# D1-Mini_Adapter.net
KiCad netlist of a schematic drawn in EAGLE
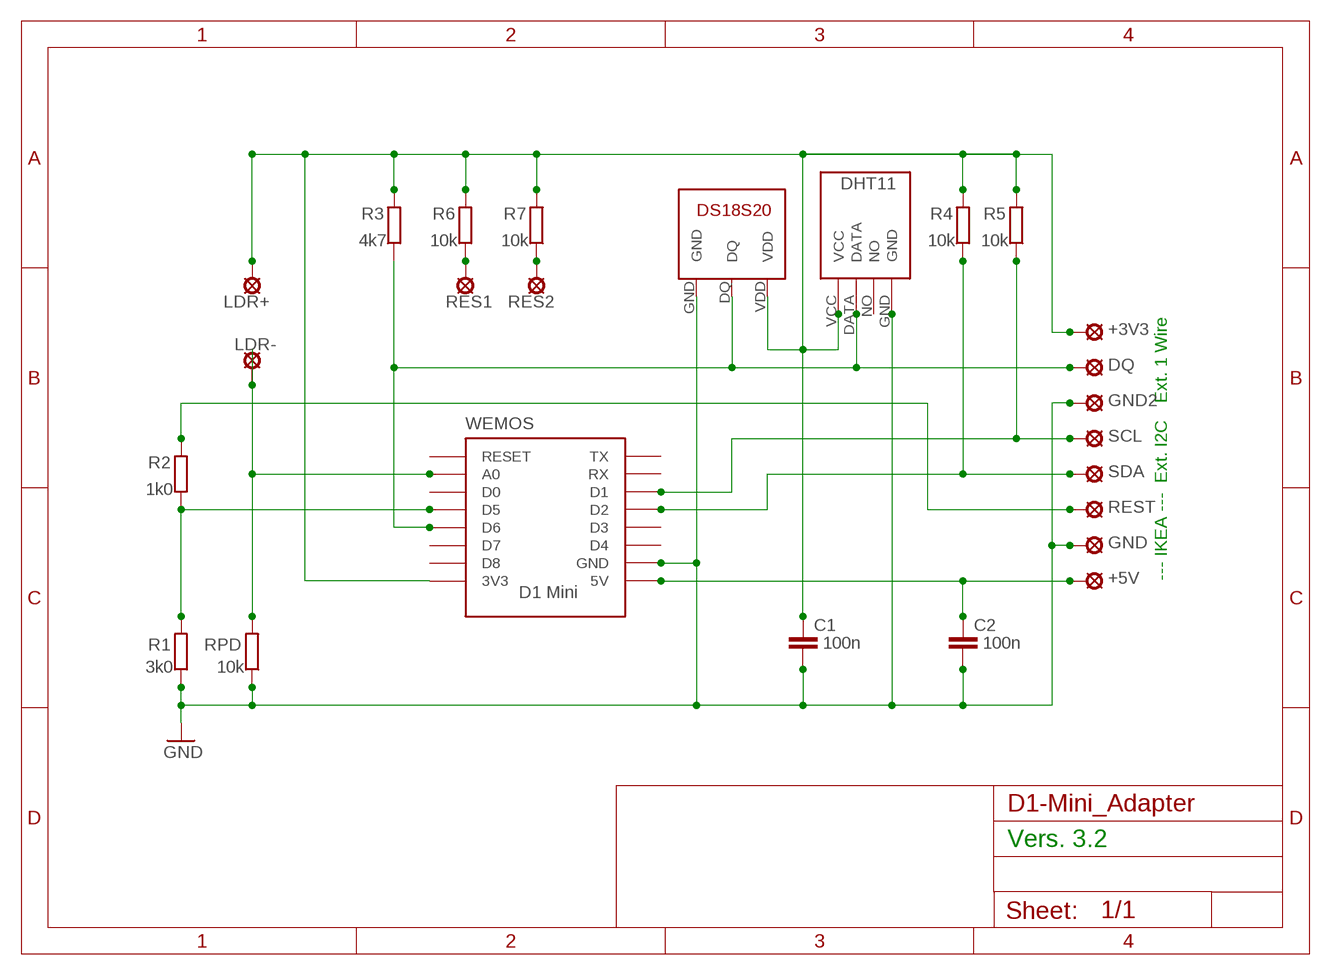
[diagram p0: schematic, sheet 1]

(export (version "E")
  (design (tool "Eeschema 10.0.6"))
  (components
    (comp (ref "+3V3")
      (value "SE13")
      (footprint "eagle-import:SE13")
      (libsource (lib "eagle-import") (part "SE13"))
    )
    (comp (ref "+5V")
      (value "SE13")
      (footprint "eagle-import:SE13")
      (libsource (lib "eagle-import") (part "SE13"))
    )
    (comp (ref "C1")
      (value "100n")
      (footprint "eagle-import:C025_050-045X075")
      (libsource (lib "eagle-import") (part "C-EU025_050-045X075"))
    )
    (comp (ref "C2")
      (value "100n")
      (footprint "eagle-import:C025_050-045X075")
      (libsource (lib "eagle-import") (part "C-EU025_050-045X075"))
    )
    (comp (ref "DQ")
      (value "SE13")
      (footprint "eagle-import:SE13")
      (libsource (lib "eagle-import") (part "SE13"))
    )
    (comp (ref "DS1820")
      (value "DS18S20")
      (footprint "eagle-import:DS18S20-PACKAGE")
      (libsource (lib "eagle-import") (part "DS18S20"))
    )
    (comp (ref "GND")
      (value "SE13")
      (footprint "eagle-import:SE13")
      (libsource (lib "eagle-import") (part "SE13"))
    )
    (comp (ref "GND2")
      (value "SE13")
      (footprint "eagle-import:SE13")
      (libsource (lib "eagle-import") (part "SE13"))
    )
    (comp (ref "LDR+")
      (value "SE13")
      (footprint "eagle-import:SE13")
      (libsource (lib "eagle-import") (part "SE13"))
    )
    (comp (ref "LDR-")
      (value "SE13")
      (footprint "eagle-import:SE13")
      (libsource (lib "eagle-import") (part "SE13"))
    )
    (comp (ref "R1")
      (value "3k0")
      (footprint "eagle-import:0207_10")
      (libsource (lib "eagle-import") (part "R-EU_0207/10"))
    )
    (comp (ref "R2")
      (value "1k0")
      (footprint "eagle-import:0207_10")
      (libsource (lib "eagle-import") (part "R-EU_0207/10"))
    )
    (comp (ref "R3")
      (value "4k7")
      (footprint "eagle-import:0207_10")
      (libsource (lib "eagle-import") (part "R-EU_0207/10"))
    )
    (comp (ref "R4")
      (value "10k")
      (footprint "eagle-import:0207_10")
      (libsource (lib "eagle-import") (part "R-EU_0207/10"))
    )
    (comp (ref "R5")
      (value "10k")
      (footprint "eagle-import:0207_10")
      (libsource (lib "eagle-import") (part "R-EU_0207/10"))
    )
    (comp (ref "R6")
      (value "10k")
      (footprint "eagle-import:0207_10")
      (libsource (lib "eagle-import") (part "R-EU_0207/10"))
    )
    (comp (ref "R7")
      (value "10k")
      (footprint "eagle-import:0207_10")
      (libsource (lib "eagle-import") (part "R-EU_0207/10"))
    )
    (comp (ref "RES1")
      (value "SE13")
      (footprint "eagle-import:SE13")
      (libsource (lib "eagle-import") (part "SE13"))
    )
    (comp (ref "RES2")
      (value "SE13")
      (footprint "eagle-import:SE13")
      (libsource (lib "eagle-import") (part "SE13"))
    )
    (comp (ref "REST")
      (value "SE13")
      (footprint "eagle-import:SE13")
      (libsource (lib "eagle-import") (part "SE13"))
    )
    (comp (ref "RPD")
      (value "10k")
      (footprint "eagle-import:0207_10")
      (libsource (lib "eagle-import") (part "R-EU_0207/10"))
    )
    (comp (ref "SCL")
      (value "SE13")
      (footprint "eagle-import:SE13")
      (libsource (lib "eagle-import") (part "SE13"))
    )
    (comp (ref "SDA")
      (value "SE13")
      (footprint "eagle-import:SE13")
      (libsource (lib "eagle-import") (part "SE13"))
    )
    (comp (ref "U$1")
      (value "DHT11-PION.")
      (footprint "eagle-import:DHT11-PION.")
      (libsource (lib "eagle-import") (part "DHT11-PION."))
    )
    (comp (ref "WEMOS")
      (value "D1 Mini")
      (footprint "eagle-import:WEMOS-D1-MINI")
      (libsource (lib "eagle-import") (part "WEMOS-D1-MINI"))
    )
  )
  (nets
    (net (code "1") (name "GND") (class "Default")
      (node (ref "C1") (pin "2") (pinfunction "2_2") (pintype "passive"))
      (node (ref "C2") (pin "2") (pinfunction "2_2") (pintype "passive"))
      (node (ref "DS1820") (pin "GND") (pinfunction "GND_GND") (pintype "power_in"))
      (node (ref "GND") (pin "MP") (pinfunction "MP_MP") (pintype "passive"))
      (node (ref "GND2") (pin "MP") (pinfunction "MP_MP") (pintype "passive"))
      (node (ref "R1") (pin "1") (pinfunction "1_1") (pintype "passive"))
      (node (ref "RPD") (pin "1") (pinfunction "1_1") (pintype "passive"))
      (node (ref "U$1") (pin "GND") (pinfunction "GND_GND") (pintype "bidirectional"))
      (node (ref "WEMOS") (pin "GND") (pinfunction "GND_GND") (pintype "bidirectional"))
    )
    (net (code "2") (name "Net-(+3V3-PadMP)") (class "Default")
      (node (ref "+3V3") (pin "MP") (pinfunction "MP_MP") (pintype "passive"))
      (node (ref "C1") (pin "1") (pinfunction "1_1") (pintype "passive"))
      (node (ref "DS1820") (pin "VDD") (pinfunction "VDD_VDD") (pintype "power_in"))
      (node (ref "LDR+") (pin "MP") (pinfunction "MP_MP") (pintype "passive"))
      (node (ref "R3") (pin "2") (pinfunction "2_2") (pintype "passive"))
      (node (ref "R4") (pin "2") (pinfunction "2_2") (pintype "passive"))
      (node (ref "R5") (pin "2") (pinfunction "2_2") (pintype "passive"))
      (node (ref "R6") (pin "2") (pinfunction "2_2") (pintype "passive"))
      (node (ref "R7") (pin "2") (pinfunction "2_2") (pintype "passive"))
      (node (ref "U$1") (pin "VCC") (pinfunction "VCC_VCC") (pintype "bidirectional"))
      (node (ref "WEMOS") (pin "3V3") (pinfunction "3V3_3V3") (pintype "bidirectional"))
    )
    (net (code "3") (name "Net-(+5V-PadMP)") (class "Default")
      (node (ref "+5V") (pin "MP") (pinfunction "MP_MP") (pintype "passive"))
      (node (ref "C2") (pin "1") (pinfunction "1_1") (pintype "passive"))
      (node (ref "WEMOS") (pin "5V") (pinfunction "5V_5V") (pintype "bidirectional"))
    )
    (net (code "4") (name "Net-(DQ-PadMP)") (class "Default")
      (node (ref "DQ") (pin "MP") (pinfunction "MP_MP") (pintype "passive"))
      (node (ref "DS1820") (pin "DQ") (pinfunction "DQ_DQ") (pintype "bidirectional"))
      (node (ref "R3") (pin "1") (pinfunction "1_1") (pintype "passive"))
      (node (ref "U$1") (pin "DATA") (pinfunction "DATA_DATA") (pintype "bidirectional"))
      (node (ref "WEMOS") (pin "D6") (pinfunction "D6_D6") (pintype "bidirectional"))
    )
    (net (code "5") (name "Net-(LDR--PadMP)") (class "Default")
      (node (ref "LDR-") (pin "MP") (pinfunction "MP_MP") (pintype "passive"))
      (node (ref "RPD") (pin "2") (pinfunction "2_2") (pintype "passive"))
      (node (ref "WEMOS") (pin "A0") (pinfunction "A0_A0") (pintype "bidirectional"))
    )
    (net (code "6") (name "Net-(R1-Pad2)") (class "Default")
      (node (ref "R1") (pin "2") (pinfunction "2_2") (pintype "passive"))
      (node (ref "R2") (pin "1") (pinfunction "1_1") (pintype "passive"))
      (node (ref "WEMOS") (pin "D5") (pinfunction "D5_D5") (pintype "bidirectional"))
    )
    (net (code "7") (name "Net-(R2-Pad2)") (class "Default")
      (node (ref "R2") (pin "2") (pinfunction "2_2") (pintype "passive"))
      (node (ref "REST") (pin "MP") (pinfunction "MP_MP") (pintype "passive"))
    )
    (net (code "8") (name "Net-(R4-Pad1)") (class "Default")
      (node (ref "R4") (pin "1") (pinfunction "1_1") (pintype "passive"))
      (node (ref "SDA") (pin "MP") (pinfunction "MP_MP") (pintype "passive"))
      (node (ref "WEMOS") (pin "D2") (pinfunction "D2_D2") (pintype "bidirectional"))
    )
    (net (code "9") (name "Net-(R5-Pad1)") (class "Default")
      (node (ref "R5") (pin "1") (pinfunction "1_1") (pintype "passive"))
      (node (ref "SCL") (pin "MP") (pinfunction "MP_MP") (pintype "passive"))
      (node (ref "WEMOS") (pin "D1") (pinfunction "D1_D1") (pintype "bidirectional"))
    )
    (net (code "10") (name "Net-(R6-Pad1)") (class "Default")
      (node (ref "R6") (pin "1") (pinfunction "1_1") (pintype "passive"))
      (node (ref "RES1") (pin "MP") (pinfunction "MP_MP") (pintype "passive"))
    )
    (net (code "11") (name "Net-(R7-Pad1)") (class "Default")
      (node (ref "R7") (pin "1") (pinfunction "1_1") (pintype "passive"))
      (node (ref "RES2") (pin "MP") (pinfunction "MP_MP") (pintype "passive"))
    )
    (net (code "12") (name "unconnected-(U$1-PadNO)") (class "Default")
      (node (ref "U$1") (pin "NO") (pinfunction "NO_NO") (pintype "bidirectional"))
    )
    (net (code "13") (name "unconnected-(WEMOS-PadD0)") (class "Default")
      (node (ref "WEMOS") (pin "D0") (pinfunction "D0_D0") (pintype "bidirectional"))
    )
    (net (code "14") (name "unconnected-(WEMOS-PadD3)") (class "Default")
      (node (ref "WEMOS") (pin "D3") (pinfunction "D3_D3") (pintype "bidirectional"))
    )
    (net (code "15") (name "unconnected-(WEMOS-PadD4)") (class "Default")
      (node (ref "WEMOS") (pin "D4") (pinfunction "D4_D4") (pintype "bidirectional"))
    )
    (net (code "16") (name "unconnected-(WEMOS-PadD7)") (class "Default")
      (node (ref "WEMOS") (pin "D7") (pinfunction "D7_D7") (pintype "bidirectional"))
    )
    (net (code "17") (name "unconnected-(WEMOS-PadD8)") (class "Default")
      (node (ref "WEMOS") (pin "D8") (pinfunction "D8_D8") (pintype "bidirectional"))
    )
    (net (code "18") (name "unconnected-(WEMOS-PadRESET)") (class "Default")
      (node (ref "WEMOS") (pin "RESET") (pinfunction "RESET_RESET") (pintype "bidirectional"))
    )
    (net (code "19") (name "unconnected-(WEMOS-PadRX)") (class "Default")
      (node (ref "WEMOS") (pin "RX") (pinfunction "RX_RX") (pintype "bidirectional"))
    )
    (net (code "20") (name "unconnected-(WEMOS-PadTX)") (class "Default")
      (node (ref "WEMOS") (pin "TX") (pinfunction "TX_TX") (pintype "bidirectional"))
    )
  )
)
